# CSMSF.net
KiCad netlist of a schematic drawn in Altium Designer
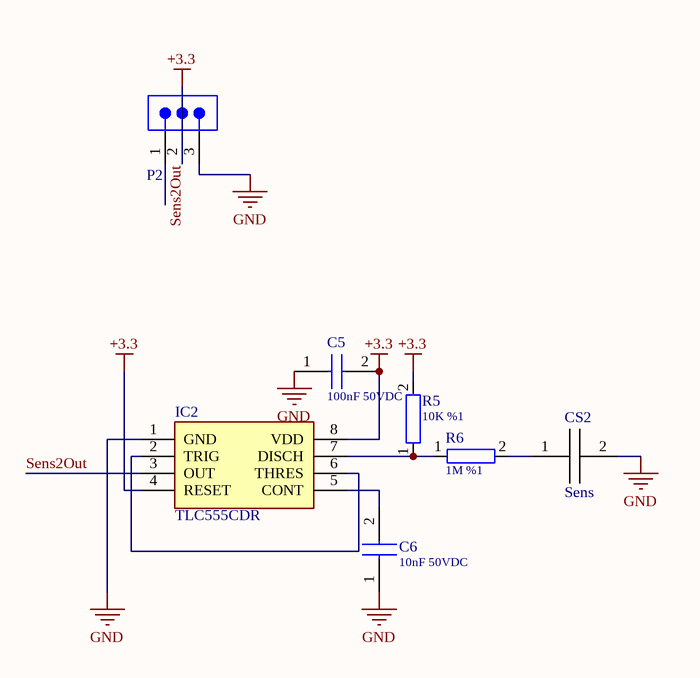
[diagram p0: CSMSF.SchDoc]

(export (version "E")
  (design (tool "Eeschema 10.0.6"))
  (components
    (comp (ref "C5")
      (value "100nF 50VDC")
      (footprint "0603 CAP")
      (description "100nF 50VDC ±10% X7R MLCC 0603")
      (fields (field (name "Comment") "CL10B104KB8NNNC"))
      (libsource (lib "CSMS") (part "CL10B104KB8NNNC"))
    )
    (comp (ref "C6")
      (value "10nF 50VDC")
      (footprint "0603 CAP")
      (description "10nF, 50 V, ± 10%, X7R, 0603, Multilayer Ceramic Capacitor,")
      (fields (field (name "Comment") "CC0603KRX7R9BB103"))
      (libsource (lib "CSMS") (part "CC0603KRX7R9BB103"))
    )
    (comp (ref "CS2")
      (value "Sens")
      (footprint "Sens")
      (description "Pcb Sens")
      (libsource (lib "CSMS") (part "Sens"))
    )
    (comp (ref "IC2")
      (value "TLC555CDR")
      (footprint "SOIC127P600X175-8N")
      (description "555 Astable 2.1-MHz, 250-µA, Low-Power Timer 8-SOIC 0 to 70")
      (fields (field (name "MOUSER PART NUMBER") "595-TLC555CDR"))
      (libsource (lib "CSMS") (part "TLC555CDR"))
    )
    (comp (ref "P2")
      (value "61300311021")
      (footprint "61300311021")
      (description "WR-PHD Pin Header, THT, Angled, pitch 2.54mm, 1 Row, 3P")
      (fields (field (name "MANUFACTURER") "Wurth Elektronik"))
      (libsource (lib "CSMS") (part "61300311021"))
    )
    (comp (ref "R5")
      (value "10K %1")
      (footprint "0603 RES")
      (description "10K Ohms 1% 1/10W-S 100PPM RES 0603")
      (fields (field (name "Comment") "0603SAF1002T5E"))
      (libsource (lib "CSMS") (part "0603SAF1002T5E"))
    )
    (comp (ref "R6")
      (value "1M %1")
      (footprint "0603 RES")
      (description "1M Ohms 1% 1/10W-S 100PPM RES 0603")
      (fields (field (name "Comment") "0603SAF1004T5E"))
      (libsource (lib "CSMS") (part "0603SAF1004T5E"))
    )
  )
  (nets
    (net (code "1") (name "+3.3") (class "Default")
      (node (ref "C5") (pin "2") (pinfunction "2_2") (pintype "passive"))
      (node (ref "IC2") (pin "4") (pinfunction "RESET_4") (pintype "passive"))
      (node (ref "IC2") (pin "8") (pinfunction "VDD_8") (pintype "passive"))
      (node (ref "P2") (pin "2") (pinfunction "2_2") (pintype "passive"))
      (node (ref "R5") (pin "2") (pinfunction "2_2") (pintype "passive"))
    )
    (net (code "2") (name "/Sens2Out") (class "Default")
      (node (ref "IC2") (pin "3") (pinfunction "OUT_3") (pintype "passive"))
      (node (ref "P2") (pin "1") (pinfunction "1_1") (pintype "passive"))
    )
    (net (code "3") (name "GND") (class "Default")
      (node (ref "C5") (pin "1") (pinfunction "1_1") (pintype "passive"))
      (node (ref "C6") (pin "1") (pinfunction "1_1") (pintype "passive"))
      (node (ref "CS2") (pin "2") (pinfunction "2_2") (pintype "passive"))
      (node (ref "IC2") (pin "1") (pinfunction "GND_1") (pintype "passive"))
      (node (ref "P2") (pin "3") (pinfunction "3_3") (pintype "passive"))
    )
    (net (code "4") (name "Net-(CS2-Pad1)") (class "Default")
      (node (ref "CS2") (pin "1") (pinfunction "1_1") (pintype "passive"))
      (node (ref "R6") (pin "2") (pinfunction "2_2") (pintype "passive"))
    )
    (net (code "5") (name "Net-(IC2-CONT)") (class "Default")
      (node (ref "C6") (pin "2") (pinfunction "2_2") (pintype "passive"))
      (node (ref "IC2") (pin "5") (pinfunction "CONT_5") (pintype "passive"))
    )
    (net (code "6") (name "Net-(IC2-DISCH)") (class "Default")
      (node (ref "IC2") (pin "7") (pinfunction "DISCH_7") (pintype "passive"))
      (node (ref "R5") (pin "1") (pinfunction "1_1") (pintype "passive"))
      (node (ref "R6") (pin "1") (pinfunction "1_1") (pintype "passive"))
    )
    (net (code "7") (name "Net-(IC2-THRES)") (class "Default")
      (node (ref "IC2") (pin "2") (pinfunction "TRIG_2") (pintype "passive"))
      (node (ref "IC2") (pin "6") (pinfunction "THRES_6") (pintype "passive"))
    )
  )
)
